# Master_ESP32WROOM.net
KiCad netlist of a schematic drawn in Altium Designer
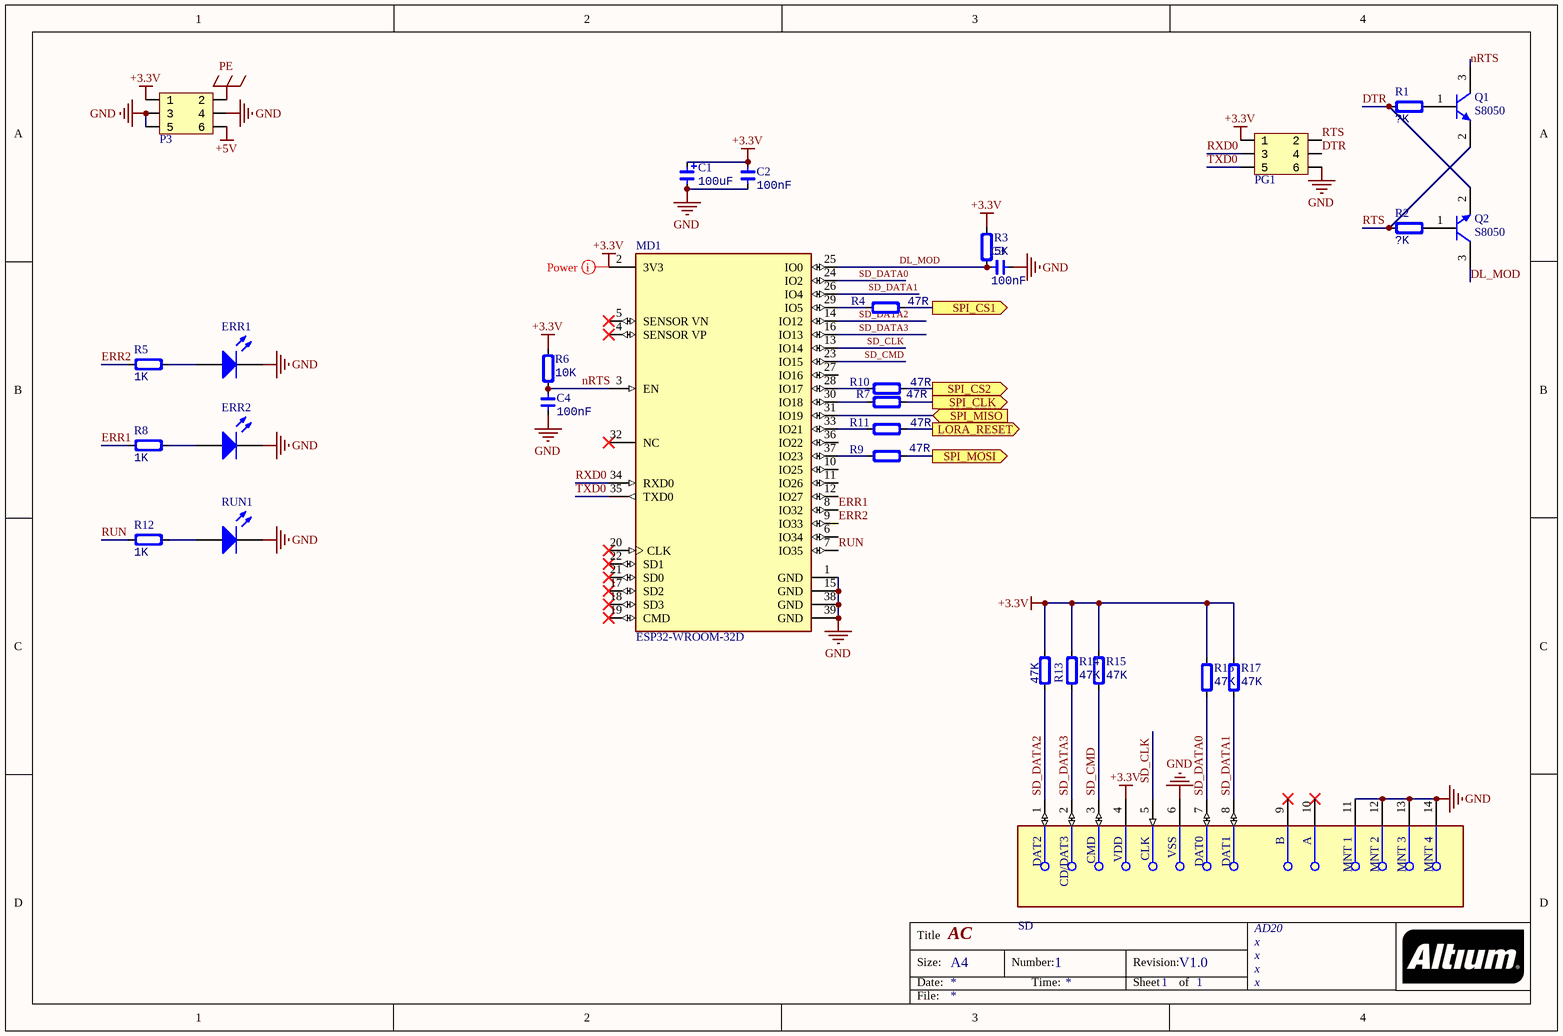
[diagram p0: [Master]ESP32WROOM.SchDoc]

(export (version "E")
  (design (tool "Eeschema 10.0.6"))
  (components
    (comp (ref "C1")
      (value "100uF")
      (footprint "CAP_TAN_1206")
      (description "Capacitor Tantalum")
      (fields (field (name "Comment") "C1206"))
      (libsource (lib "Integrated_Library") (part "Cap_Tan_1206"))
    )
    (comp (ref "C2")
      (value "100nF")
      (footprint "CAP-0805")
      (description "Capacitor")
      (fields (field (name "Comment") "Cap_0805"))
      (libsource (lib "Integrated_Library") (part "Cap_0805"))
    )
    (comp (ref "C3")
      (value "100nF")
      (footprint "CAP-0603")
      (description "Capacitor")
      (fields (field (name "Comment") "Cap_0603"))
      (libsource (lib "") (part "Cap_0603_1"))
    )
    (comp (ref "C4")
      (value "100nF")
      (footprint "CAP-0603")
      (description "Capacitor")
      (fields (field (name "Comment") "Cap_0603"))
      (libsource (lib "Integrated_Library") (part "Cap_0603"))
    )
    (comp (ref "ERR1")
      (value "150080YS75000")
      (footprint "0805_A")
      (description "SMD mono-color Chip LED, WL-SMCW, Yellow")
      (fields (field (name "MANUFACTURER") "Wuerth Elektronik"))
      (libsource (lib "Altium Content Vault") (part "WE-LED_K1A2-2"))
    )
    (comp (ref "ERR2")
      (value "150080YS75000")
      (footprint "0805_A")
      (description "SMD mono-color Chip LED, WL-SMCW, Yellow")
      (fields (field (name "MANUFACTURER") "Wuerth Elektronik"))
      (libsource (lib "Altium Content Vault") (part "WE-LED_K1A2-2"))
    )
    (comp (ref "MD1")
      (value "ESP32-WROOM-32D")
      (footprint "FP-ESP32-WROOM-32D-MFG")
      (description "WIFI MODULE 32MBITS SPI FLASH")
      (fields
        (field (name "OCTOPART") "https://octopart.com/esp32-wroom-32d-espressif+systems-91040050")
        (field (name "MANUFACTURER") "Espressif Systems")
      )
      (libsource (lib "Altium Content Vault") (part "a031a76f8c27026a7a7f4657ff233a3"))
    )
    (comp (ref "P3")
      (value "HDR2x3")
      (footprint "HDR2X3_2.54_90F")
      (description "Header")
      (libsource (lib "Integrated_Library") (part "HDR2x3_2.54"))
    )
    (comp (ref "PG1")
      (value "HDR2x3")
      (footprint "HDR2X3_2.54_90F")
      (description "Header")
      (libsource (lib "Integrated_Library") (part "HDR2x3_2.54"))
    )
    (comp (ref "Q1")
      (value "S8050")
      (footprint "ONSC-SOT-23-3-318-08_V")
      (description "High Voltage Transistor, NPN Silicon, 3-Pin SOT-23, Pb-Free, Tape and Reel")
      (fields (field (name "PARTNUMBER") "MMBTA42LT1G") (field (name "MANUFACTURER") "On Semiconductor"))
      (libsource (lib "Altium Content Vault") (part "ONSC-NPN-B1E2C3-3"))
    )
    (comp (ref "Q2")
      (value "S8050")
      (footprint "ONSC-SOT-23-3-318-08_V")
      (description "High Voltage Transistor, NPN Silicon, 3-Pin SOT-23, Pb-Free, Tape and Reel")
      (fields (field (name "PARTNUMBER") "MMBTA42LT1G") (field (name "MANUFACTURER") "On Semiconductor"))
      (libsource (lib "Altium Content Vault") (part "ONSC-NPN-B1E2C3-3"))
    )
    (comp (ref "R1")
      (value "?K")
      (footprint "RES-0805")
      (description "Resistor")
      (fields (field (name "Comment") "R0805"))
      (libsource (lib "Integrated_Library") (part "Res_0805"))
    )
    (comp (ref "R2")
      (value "?K")
      (footprint "RES-0805")
      (description "Resistor")
      (fields (field (name "Comment") "R0805"))
      (libsource (lib "Integrated_Library") (part "Res_0805"))
    )
    (comp (ref "R3")
      (value "5K")
      (footprint "RES-0805")
      (description "Resistor")
      (fields (field (name "Comment") "R0805"))
      (libsource (lib "Integrated_Library") (part "Res_0805"))
    )
    (comp (ref "R4")
      (value "47R")
      (footprint "RES-0805")
      (description "Resistor")
      (fields (field (name "Comment") "R0805"))
      (libsource (lib "Integrated_Library") (part "Res_0805"))
    )
    (comp (ref "R5")
      (value "1K")
      (footprint "RES-0805")
      (description "Resistor")
      (fields (field (name "Comment") "R0805"))
      (libsource (lib "Integrated_Library") (part "Res_0805"))
    )
    (comp (ref "R6")
      (value "10K")
      (footprint "RES-0805")
      (description "Resistor")
      (fields (field (name "Comment") "R0805"))
      (libsource (lib "Integrated_Library") (part "Res_0805"))
    )
    (comp (ref "R7")
      (value "47R")
      (footprint "RES-0805")
      (description "Resistor")
      (fields (field (name "Comment") "R0805"))
      (libsource (lib "Integrated_Library") (part "Res_0805"))
    )
    (comp (ref "R8")
      (value "1K")
      (footprint "RES-0805")
      (description "Resistor")
      (fields (field (name "Comment") "R0805"))
      (libsource (lib "Integrated_Library") (part "Res_0805"))
    )
    (comp (ref "R9")
      (value "47R")
      (footprint "RES-0805")
      (description "Resistor")
      (fields (field (name "Comment") "R0805"))
      (libsource (lib "Integrated_Library") (part "Res_0805"))
    )
    (comp (ref "R10")
      (value "47R")
      (footprint "RES-0805")
      (description "Resistor")
      (fields (field (name "Comment") "R0805"))
      (libsource (lib "Integrated_Library") (part "Res_0805"))
    )
    (comp (ref "R11")
      (value "47R")
      (footprint "RES-0805")
      (description "Resistor")
      (fields (field (name "Comment") "R0805"))
      (libsource (lib "Integrated_Library") (part "Res_0805"))
    )
    (comp (ref "R12")
      (value "1K")
      (footprint "RES-0805")
      (description "Resistor")
      (fields (field (name "Comment") "R0805"))
      (libsource (lib "Integrated_Library") (part "Res_0805"))
    )
    (comp (ref "R13")
      (value "47K")
      (footprint "RES-0805")
      (description "Resistor")
      (fields (field (name "Comment") "R0805"))
      (libsource (lib "Integrated_Library") (part "Res_0805"))
    )
    (comp (ref "R14")
      (value "47K")
      (footprint "RES-0805")
      (description "Resistor")
      (fields (field (name "Comment") "R0805"))
      (libsource (lib "Integrated_Library") (part "Res_0805"))
    )
    (comp (ref "R15")
      (value "47K")
      (footprint "RES-0805")
      (description "Resistor")
      (fields (field (name "Comment") "R0805"))
      (libsource (lib "Integrated_Library") (part "Res_0805"))
    )
    (comp (ref "R16")
      (value "47K")
      (footprint "RES-0805")
      (description "Resistor")
      (fields (field (name "Comment") "R0805"))
      (libsource (lib "Integrated_Library") (part "Res_0805"))
    )
    (comp (ref "R17")
      (value "47K")
      (footprint "RES-0805")
      (description "Resistor")
      (fields (field (name "Comment") "R0805"))
      (libsource (lib "Integrated_Library") (part "Res_0805"))
    )
    (comp (ref "RUN1")
      (value "150080YS75000")
      (footprint "0805_A")
      (description "SMD mono-color Chip LED, WL-SMCW, Yellow")
      (fields (field (name "MANUFACTURER") "Wuerth Elektronik"))
      (libsource (lib "Altium Content Vault") (part "WE-LED_K1A2-2"))
    )
    (comp (ref "SD")
      (value "DM3AT-SF-PEJM5(11)")
      (footprint "FP-DM3AT-SF-PEJM5_11-MFG")
      (description "CONN MICRO SD R/A PUSH-PUSH SMD")
      (fields
        (field (name "MANUFACTURER") "Hirose")
        (field (name "OCTOPART") "https://octopart.com/dm3at-sf-pejm5%2811%29-hirose-29719365")
      )
      (libsource (lib "Integrated_Library") (part "MicroSDCARD"))
    )
  )
  (nets
    (net (code "1") (name "+3.3V") (class "Default")
      (node (ref "C1") (pin "1") (pinfunction "1_1") (pintype "passive"))
      (node (ref "C2") (pin "2") (pinfunction "2_2") (pintype "passive"))
      (node (ref "MD1") (pin "2") (pinfunction "3V3_2") (pintype "power_in"))
      (node (ref "P3") (pin "1") (pinfunction "1_1") (pintype "passive"))
      (node (ref "PG1") (pin "1") (pinfunction "1_1") (pintype "passive"))
      (node (ref "R13") (pin "1") (pinfunction "1_1") (pintype "passive"))
      (node (ref "R14") (pin "1") (pinfunction "1_1") (pintype "passive"))
      (node (ref "R15") (pin "1") (pinfunction "1_1") (pintype "passive"))
      (node (ref "R16") (pin "1") (pinfunction "1_1") (pintype "passive"))
      (node (ref "R17") (pin "1") (pinfunction "1_1") (pintype "passive"))
      (node (ref "R3") (pin "1") (pinfunction "1_1") (pintype "passive"))
      (node (ref "R6") (pin "1") (pinfunction "1_1") (pintype "passive"))
      (node (ref "SD") (pin "4") (pinfunction "VDD_4") (pintype "power_in"))
    )
    (net (code "2") (name "+5V") (class "Default")
      (node (ref "P3") (pin "6") (pinfunction "6_6") (pintype "passive"))
    )
    (net (code "3") (name "/DL_MOD") (class "Default")
      (node (ref "C3") (pin "2") (pinfunction "2_2") (pintype "passive"))
      (node (ref "MD1") (pin "25") (pinfunction "IO0_25") (pintype "bidirectional"))
      (node (ref "Q2") (pin "3") (pinfunction "C_3") (pintype "passive"))
      (node (ref "R3") (pin "2") (pinfunction "2_2") (pintype "passive"))
    )
    (net (code "4") (name "/DTR") (class "Default")
      (node (ref "PG1") (pin "4") (pinfunction "4_4") (pintype "passive"))
      (node (ref "Q2") (pin "2") (pinfunction "E_2") (pintype "passive"))
      (node (ref "R1") (pin "1") (pinfunction "1_1") (pintype "passive"))
    )
    (net (code "5") (name "/ERR1") (class "Default")
      (node (ref "MD1") (pin "8") (pinfunction "IO32_8") (pintype "bidirectional"))
      (node (ref "R8") (pin "2") (pinfunction "2_2") (pintype "passive"))
    )
    (net (code "6") (name "/ERR2") (class "Default")
      (node (ref "MD1") (pin "9") (pinfunction "IO33_9") (pintype "bidirectional"))
      (node (ref "R5") (pin "2") (pinfunction "2_2") (pintype "passive"))
    )
    (net (code "7") (name "/LORA_RESET") (class "Default")
      (node (ref "R11") (pin "2") (pinfunction "2_2") (pintype "passive"))
    )
    (net (code "8") (name "/RTS") (class "Default")
      (node (ref "PG1") (pin "2") (pinfunction "2_2") (pintype "passive"))
      (node (ref "Q1") (pin "2") (pinfunction "E_2") (pintype "passive"))
      (node (ref "R2") (pin "1") (pinfunction "1_1") (pintype "passive"))
    )
    (net (code "9") (name "/RUN") (class "Default")
      (node (ref "MD1") (pin "7") (pinfunction "IO35_7") (pintype "bidirectional"))
      (node (ref "R12") (pin "2") (pinfunction "2_2") (pintype "passive"))
    )
    (net (code "10") (name "/RXD0") (class "Default")
      (node (ref "MD1") (pin "34") (pinfunction "RXD0_34") (pintype "input"))
      (node (ref "PG1") (pin "3") (pinfunction "3_3") (pintype "passive"))
    )
    (net (code "11") (name "/SD_CLK") (class "Default")
      (node (ref "MD1") (pin "13") (pinfunction "IO14_13") (pintype "bidirectional"))
      (node (ref "SD") (pin "5") (pinfunction "CLK_5") (pintype "input"))
    )
    (net (code "12") (name "/SD_CMD") (class "Default")
      (node (ref "MD1") (pin "23") (pinfunction "IO15_23") (pintype "bidirectional"))
      (node (ref "R15") (pin "2") (pinfunction "2_2") (pintype "passive"))
      (node (ref "SD") (pin "3") (pinfunction "CMD_3") (pintype "bidirectional"))
    )
    (net (code "13") (name "/SD_DATA0") (class "Default")
      (node (ref "MD1") (pin "24") (pinfunction "IO2_24") (pintype "bidirectional"))
      (node (ref "R16") (pin "2") (pinfunction "2_2") (pintype "passive"))
      (node (ref "SD") (pin "7") (pinfunction "DAT0_7") (pintype "bidirectional"))
    )
    (net (code "14") (name "/SD_DATA1") (class "Default")
      (node (ref "MD1") (pin "26") (pinfunction "IO4_26") (pintype "bidirectional"))
      (node (ref "R17") (pin "2") (pinfunction "2_2") (pintype "passive"))
      (node (ref "SD") (pin "8") (pinfunction "DAT1_8") (pintype "bidirectional"))
    )
    (net (code "15") (name "/SD_DATA2") (class "Default")
      (node (ref "MD1") (pin "14") (pinfunction "IO12_14") (pintype "bidirectional"))
      (node (ref "R13") (pin "2") (pinfunction "2_2") (pintype "passive"))
      (node (ref "SD") (pin "1") (pinfunction "DAT2_1") (pintype "bidirectional"))
    )
    (net (code "16") (name "/SD_DATA3") (class "Default")
      (node (ref "MD1") (pin "16") (pinfunction "IO13_16") (pintype "bidirectional"))
      (node (ref "R14") (pin "2") (pinfunction "2_2") (pintype "passive"))
      (node (ref "SD") (pin "2") (pinfunction "CD/DAT3_2") (pintype "bidirectional"))
    )
    (net (code "17") (name "/SPI_CLK") (class "Default")
      (node (ref "R7") (pin "2") (pinfunction "2_2") (pintype "passive"))
    )
    (net (code "18") (name "/SPI_CS1") (class "Default")
      (node (ref "R4") (pin "2") (pinfunction "2_2") (pintype "passive"))
    )
    (net (code "19") (name "/SPI_CS2") (class "Default")
      (node (ref "R10") (pin "2") (pinfunction "2_2") (pintype "passive"))
    )
    (net (code "20") (name "/SPI_MISO") (class "Default")
      (node (ref "MD1") (pin "31") (pinfunction "IO19_31") (pintype "bidirectional"))
    )
    (net (code "21") (name "/SPI_MOSI") (class "Default")
      (node (ref "R9") (pin "2") (pinfunction "2_2") (pintype "passive"))
    )
    (net (code "22") (name "/TXD0") (class "Default")
      (node (ref "MD1") (pin "35") (pinfunction "TXD0_35") (pintype "output"))
      (node (ref "PG1") (pin "5") (pinfunction "5_5") (pintype "passive"))
    )
    (net (code "23") (name "/nRTS") (class "Default")
      (node (ref "C4") (pin "2") (pinfunction "2_2") (pintype "passive"))
      (node (ref "MD1") (pin "3") (pinfunction "EN_3") (pintype "input"))
      (node (ref "Q1") (pin "3") (pinfunction "C_3") (pintype "passive"))
      (node (ref "R6") (pin "2") (pinfunction "2_2") (pintype "passive"))
    )
    (net (code "24") (name "GND") (class "Default")
      (node (ref "C1") (pin "2") (pinfunction "2_2") (pintype "passive"))
      (node (ref "C2") (pin "1") (pinfunction "1_1") (pintype "passive"))
      (node (ref "C3") (pin "1") (pinfunction "1_1") (pintype "passive"))
      (node (ref "C4") (pin "1") (pinfunction "1_1") (pintype "passive"))
      (node (ref "ERR1") (pin "1") (pinfunction "K_1") (pintype "passive"))
      (node (ref "ERR2") (pin "1") (pinfunction "K_1") (pintype "passive"))
      (node (ref "MD1") (pin "1") (pinfunction "GND_1") (pintype "power_in"))
      (node (ref "MD1") (pin "15") (pinfunction "GND_15") (pintype "power_in"))
      (node (ref "MD1") (pin "38") (pinfunction "GND_38") (pintype "power_in"))
      (node (ref "MD1") (pin "39") (pinfunction "GND_39") (pintype "power_in"))
      (node (ref "P3") (pin "3") (pinfunction "3_3") (pintype "passive"))
      (node (ref "P3") (pin "4") (pinfunction "4_4") (pintype "passive"))
      (node (ref "P3") (pin "5") (pinfunction "5_5") (pintype "passive"))
      (node (ref "PG1") (pin "6") (pinfunction "6_6") (pintype "passive"))
      (node (ref "RUN1") (pin "1") (pinfunction "K_1") (pintype "passive"))
      (node (ref "SD") (pin "11") (pinfunction "MNT_1_11") (pintype "passive"))
      (node (ref "SD") (pin "12") (pinfunction "MNT_2_12") (pintype "passive"))
      (node (ref "SD") (pin "13") (pinfunction "MNT_3_13") (pintype "passive"))
      (node (ref "SD") (pin "14") (pinfunction "MNT_4_14") (pintype "passive"))
      (node (ref "SD") (pin "6") (pinfunction "VSS_6") (pintype "power_in"))
    )
    (net (code "25") (name "Net-(ERR1-A)") (class "Default")
      (node (ref "ERR1") (pin "2") (pinfunction "A_2") (pintype "passive"))
      (node (ref "R5") (pin "1") (pinfunction "1_1") (pintype "passive"))
    )
    (net (code "26") (name "Net-(ERR2-A)") (class "Default")
      (node (ref "ERR2") (pin "2") (pinfunction "A_2") (pintype "passive"))
      (node (ref "R8") (pin "1") (pinfunction "1_1") (pintype "passive"))
    )
    (net (code "27") (name "Net-(MD1-IO5)") (class "Default")
      (node (ref "MD1") (pin "29") (pinfunction "IO5_29") (pintype "bidirectional"))
      (node (ref "R4") (pin "1") (pinfunction "1_1") (pintype "passive"))
    )
    (net (code "28") (name "Net-(MD1-IO17)") (class "Default")
      (node (ref "MD1") (pin "28") (pinfunction "IO17_28") (pintype "bidirectional"))
      (node (ref "R10") (pin "1") (pinfunction "1_1") (pintype "passive"))
    )
    (net (code "29") (name "Net-(MD1-IO18)") (class "Default")
      (node (ref "MD1") (pin "30") (pinfunction "IO18_30") (pintype "bidirectional"))
      (node (ref "R7") (pin "1") (pinfunction "1_1") (pintype "passive"))
    )
    (net (code "30") (name "Net-(MD1-IO21)") (class "Default")
      (node (ref "MD1") (pin "33") (pinfunction "IO21_33") (pintype "bidirectional"))
      (node (ref "R11") (pin "1") (pinfunction "1_1") (pintype "passive"))
    )
    (net (code "31") (name "Net-(MD1-IO23)") (class "Default")
      (node (ref "MD1") (pin "37") (pinfunction "IO23_37") (pintype "bidirectional"))
      (node (ref "R9") (pin "1") (pinfunction "1_1") (pintype "passive"))
    )
    (net (code "32") (name "Net-(Q1-B)") (class "Default")
      (node (ref "Q1") (pin "1") (pinfunction "B_1") (pintype "passive"))
      (node (ref "R1") (pin "2") (pinfunction "2_2") (pintype "passive"))
    )
    (net (code "33") (name "Net-(Q2-B)") (class "Default")
      (node (ref "Q2") (pin "1") (pinfunction "B_1") (pintype "passive"))
      (node (ref "R2") (pin "2") (pinfunction "2_2") (pintype "passive"))
    )
    (net (code "34") (name "Net-(RUN1-A)") (class "Default")
      (node (ref "R12") (pin "1") (pinfunction "1_1") (pintype "passive"))
      (node (ref "RUN1") (pin "2") (pinfunction "A_2") (pintype "passive"))
    )
    (net (code "35") (name "PE") (class "Default")
      (node (ref "P3") (pin "2") (pinfunction "2_2") (pintype "passive"))
    )
    (net (code "36") (name "unconnected-(MD1-CLK-Pad20)") (class "Default")
      (node (ref "MD1") (pin "20") (pinfunction "CLK_20") (pintype "input+no_connect"))
    )
    (net (code "37") (name "unconnected-(MD1-CMD-Pad19)") (class "Default")
      (node (ref "MD1") (pin "19") (pinfunction "CMD_19") (pintype "bidirectional+no_connect"))
    )
    (net (code "38") (name "unconnected-(MD1-IO16-Pad27)") (class "Default")
      (node (ref "MD1") (pin "27") (pinfunction "IO16_27") (pintype "bidirectional"))
    )
    (net (code "39") (name "unconnected-(MD1-IO22-Pad36)") (class "Default")
      (node (ref "MD1") (pin "36") (pinfunction "IO22_36") (pintype "bidirectional"))
    )
    (net (code "40") (name "unconnected-(MD1-IO25-Pad10)") (class "Default")
      (node (ref "MD1") (pin "10") (pinfunction "IO25_10") (pintype "bidirectional"))
    )
    (net (code "41") (name "unconnected-(MD1-IO26-Pad11)") (class "Default")
      (node (ref "MD1") (pin "11") (pinfunction "IO26_11") (pintype "bidirectional"))
    )
    (net (code "42") (name "unconnected-(MD1-IO27-Pad12)") (class "Default")
      (node (ref "MD1") (pin "12") (pinfunction "IO27_12") (pintype "bidirectional"))
    )
    (net (code "43") (name "unconnected-(MD1-IO34-Pad6)") (class "Default")
      (node (ref "MD1") (pin "6") (pinfunction "IO34_6") (pintype "bidirectional"))
    )
    (net (code "44") (name "unconnected-(MD1-NC-Pad32)") (class "Default")
      (node (ref "MD1") (pin "32") (pinfunction "NC_32") (pintype "passive+no_connect"))
    )
    (net (code "45") (name "unconnected-(MD1-SD0-Pad21)") (class "Default")
      (node (ref "MD1") (pin "21") (pinfunction "SD0_21") (pintype "bidirectional+no_connect"))
    )
    (net (code "46") (name "unconnected-(MD1-SD1-Pad22)") (class "Default")
      (node (ref "MD1") (pin "22") (pinfunction "SD1_22") (pintype "bidirectional+no_connect"))
    )
    (net (code "47") (name "unconnected-(MD1-SD2-Pad17)") (class "Default")
      (node (ref "MD1") (pin "17") (pinfunction "SD2_17") (pintype "bidirectional+no_connect"))
    )
    (net (code "48") (name "unconnected-(MD1-SD3-Pad18)") (class "Default")
      (node (ref "MD1") (pin "18") (pinfunction "SD3_18") (pintype "bidirectional+no_connect"))
    )
    (net (code "49") (name "unconnected-(MD1-SENSOR_VN-Pad5)") (class "Default")
      (node (ref "MD1") (pin "5") (pinfunction "SENSOR_VN_5") (pintype "bidirectional+no_connect"))
    )
    (net (code "50") (name "unconnected-(MD1-SENSOR_VP-Pad4)") (class "Default")
      (node (ref "MD1") (pin "4") (pinfunction "SENSOR_VP_4") (pintype "bidirectional+no_connect"))
    )
    (net (code "51") (name "unconnected-(SD-A-Pad10)") (class "Default")
      (node (ref "SD") (pin "10") (pinfunction "A_10") (pintype "passive+no_connect"))
    )
    (net (code "52") (name "unconnected-(SD-B-Pad9)") (class "Default")
      (node (ref "SD") (pin "9") (pinfunction "B_9") (pintype "passive+no_connect"))
    )
  )
)
